# Bargraph.net
KiCad netlist of a schematic drawn in Altium Designer
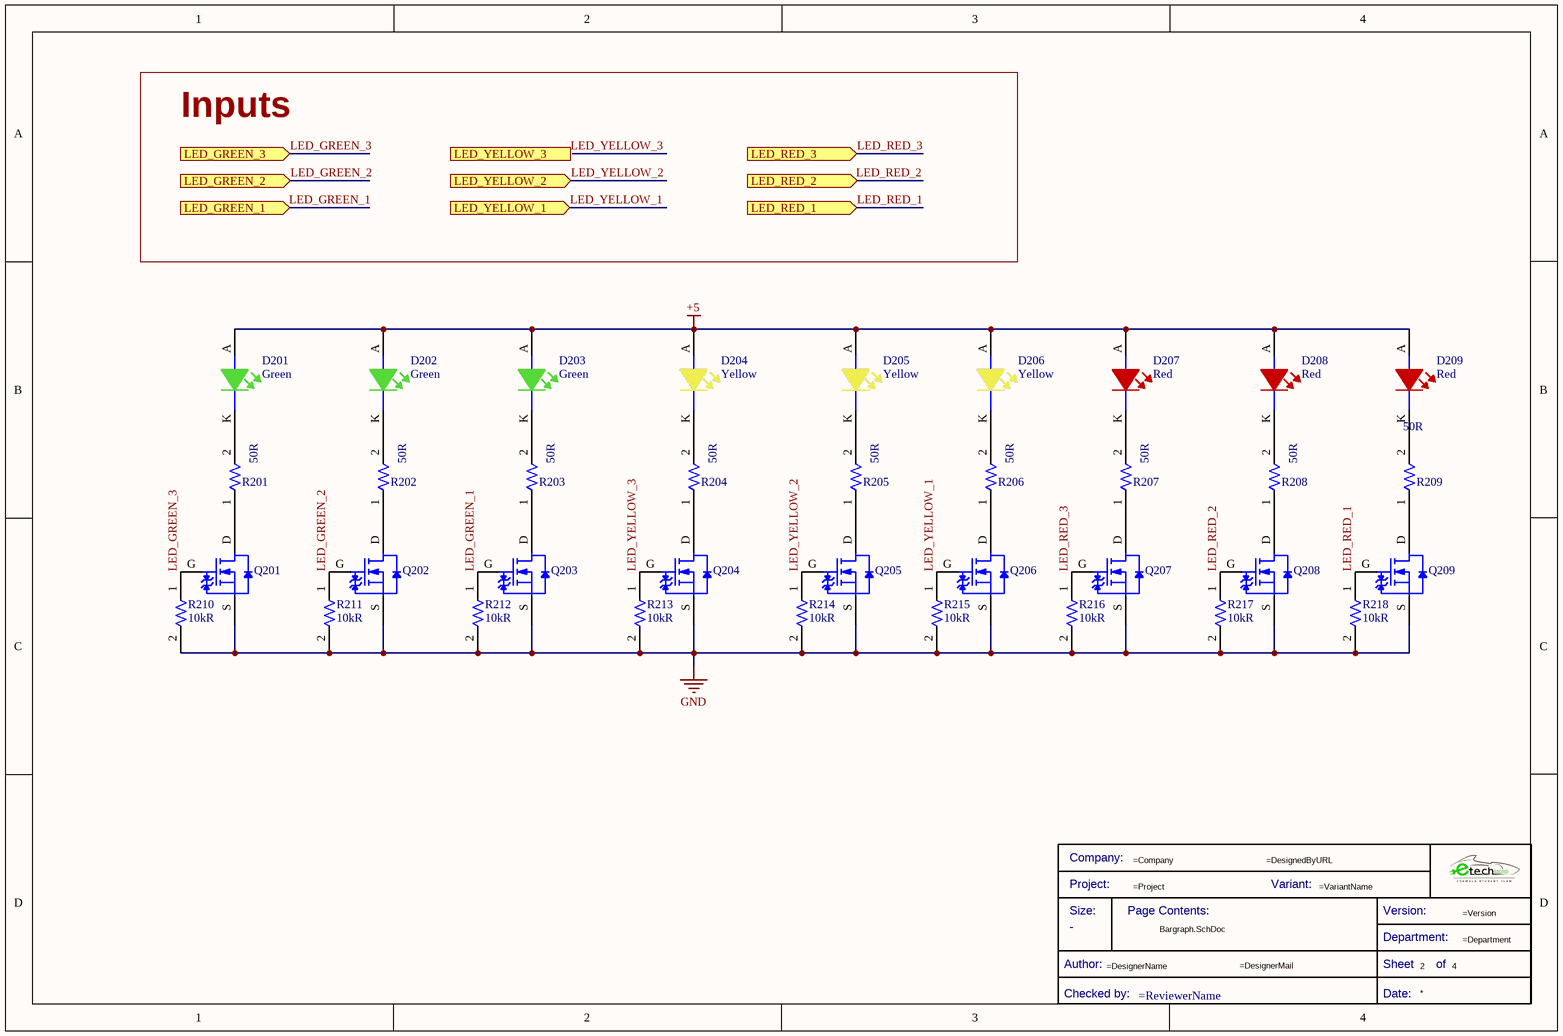
[diagram p0: Bargraph.SchDoc]

(export (version "E")
  (design (tool "Eeschema 10.0.6"))
  (components
    (comp (ref "D201")
      (value "150080GS75000")
      (footprint "LED-THT/WE/D3.9H10.5")
      (description "Led, Green, 520 Nm, 3.2 V, 30 Ma, 450 Mcd Rohs Compliant: Yes")
      (fields (field (name "COLOR") "Green") (field (name ".CREATOR") "GP"))
      (libsource (lib "Semiconductor") (part "LEDGS-THT"))
    )
    (comp (ref "D202")
      (value "150080GS75000")
      (footprint "LED-THT/WE/D3.9H10.5")
      (description "Led, Green, 520 Nm, 3.2 V, 30 Ma, 450 Mcd Rohs Compliant: Yes")
      (fields (field (name "COLOR") "Green") (field (name ".CREATOR") "GP"))
      (libsource (lib "Semiconductor") (part "LEDGS-THT"))
    )
    (comp (ref "D203")
      (value "150080GS75000")
      (footprint "LED-THT/WE/D3.9H10.5")
      (description "Led, Green, 520 Nm, 3.2 V, 30 Ma, 450 Mcd Rohs Compliant: Yes")
      (fields (field (name "COLOR") "Green") (field (name ".CREATOR") "GP"))
      (libsource (lib "Semiconductor") (part "LEDGS-THT"))
    )
    (comp (ref "D204")
      (value "150080YS75000")
      (footprint "LED-THT/WE/D3.9H10.5")
      (description "2 V Yellow LED 2012 (0805) SMD, Wurth Elektronik WL-SMCW 150080YS75000")
      (fields (field (name "COLOR") "Yellow") (field (name ".CREATOR") "DR"))
      (libsource (lib "Semiconductor") (part "LEDYS-THT"))
    )
    (comp (ref "D205")
      (value "150080YS75000")
      (footprint "LED-THT/WE/D3.9H10.5")
      (description "2 V Yellow LED 2012 (0805) SMD, Wurth Elektronik WL-SMCW 150080YS75000")
      (fields (field (name "COLOR") "Yellow") (field (name ".CREATOR") "DR"))
      (libsource (lib "Semiconductor") (part "LEDYS-THT"))
    )
    (comp (ref "D206")
      (value "150080YS75000")
      (footprint "LED-THT/WE/D3.9H10.5")
      (description "2 V Yellow LED 2012 (0805) SMD, Wurth Elektronik WL-SMCW 150080YS75000")
      (fields (field (name "COLOR") "Yellow") (field (name ".CREATOR") "DR"))
      (libsource (lib "Semiconductor") (part "LEDYS-THT"))
    )
    (comp (ref "D207")
      (value "150080RS75000")
      (footprint "LED-THT/WE/D3.9H10.5")
      (description "0805(H=0.8mm) 红色 高亮 λD=625nm VF=2V IF=30mA PD=72mW")
      (fields (field (name "COLOR") "Red") (field (name ".CREATOR") "DR"))
      (libsource (lib "Semiconductor") (part "LEDRS-THT"))
    )
    (comp (ref "D208")
      (value "150080RS75000")
      (footprint "LED-THT/WE/D3.9H10.5")
      (description "0805(H=0.8mm) 红色 高亮 λD=625nm VF=2V IF=30mA PD=72mW")
      (fields (field (name "COLOR") "Red") (field (name ".CREATOR") "DR"))
      (libsource (lib "Semiconductor") (part "LEDRS-THT"))
    )
    (comp (ref "D209")
      (value "150080RS75000")
      (footprint "LED-THT/WE/D3.9H10.5")
      (description "0805(H=0.8mm) 红色 高亮 λD=625nm VF=2V IF=30mA PD=72mW")
      (fields (field (name "COLOR") "Red") (field (name ".CREATOR") "DR"))
      (libsource (lib "Semiconductor") (part "LEDRS-THT"))
    )
    (comp (ref "Q201")
      (value "CPH3455-TL-H")
      (footprint "TRT-NCH-3/35-CPH")
      (description "CPH3455-TL-H N-channel MOSFET Transistor; 3 A; 35 V; 3-Pin CPH")
      (fields (field (name "MANUFACTURER") "ON Semiconductor") (field (name ".CREATOR") "GP"))
      (libsource (lib "Semiconductor") (part "TRT-NCH-3/35-CPH"))
    )
    (comp (ref "Q202")
      (value "CPH3455-TL-H")
      (footprint "TRT-NCH-3/35-CPH")
      (description "CPH3455-TL-H N-channel MOSFET Transistor; 3 A; 35 V; 3-Pin CPH")
      (fields (field (name "MANUFACTURER") "ON Semiconductor") (field (name ".CREATOR") "GP"))
      (libsource (lib "Semiconductor") (part "TRT-NCH-3/35-CPH"))
    )
    (comp (ref "Q203")
      (value "CPH3455-TL-H")
      (footprint "TRT-NCH-3/35-CPH")
      (description "CPH3455-TL-H N-channel MOSFET Transistor; 3 A; 35 V; 3-Pin CPH")
      (fields (field (name "MANUFACTURER") "ON Semiconductor") (field (name ".CREATOR") "GP"))
      (libsource (lib "Semiconductor") (part "TRT-NCH-3/35-CPH"))
    )
    (comp (ref "Q204")
      (value "CPH3455-TL-H")
      (footprint "TRT-NCH-3/35-CPH")
      (description "CPH3455-TL-H N-channel MOSFET Transistor; 3 A; 35 V; 3-Pin CPH")
      (fields (field (name "MANUFACTURER") "ON Semiconductor") (field (name ".CREATOR") "GP"))
      (libsource (lib "Semiconductor") (part "TRT-NCH-3/35-CPH"))
    )
    (comp (ref "Q205")
      (value "CPH3455-TL-H")
      (footprint "TRT-NCH-3/35-CPH")
      (description "CPH3455-TL-H N-channel MOSFET Transistor; 3 A; 35 V; 3-Pin CPH")
      (fields (field (name "MANUFACTURER") "ON Semiconductor") (field (name ".CREATOR") "GP"))
      (libsource (lib "Semiconductor") (part "TRT-NCH-3/35-CPH"))
    )
    (comp (ref "Q206")
      (value "CPH3455-TL-H")
      (footprint "TRT-NCH-3/35-CPH")
      (description "CPH3455-TL-H N-channel MOSFET Transistor; 3 A; 35 V; 3-Pin CPH")
      (fields (field (name "MANUFACTURER") "ON Semiconductor") (field (name ".CREATOR") "GP"))
      (libsource (lib "Semiconductor") (part "TRT-NCH-3/35-CPH"))
    )
    (comp (ref "Q207")
      (value "CPH3455-TL-H")
      (footprint "TRT-NCH-3/35-CPH")
      (description "CPH3455-TL-H N-channel MOSFET Transistor; 3 A; 35 V; 3-Pin CPH")
      (fields (field (name "MANUFACTURER") "ON Semiconductor") (field (name ".CREATOR") "GP"))
      (libsource (lib "Semiconductor") (part "TRT-NCH-3/35-CPH"))
    )
    (comp (ref "Q208")
      (value "CPH3455-TL-H")
      (footprint "TRT-NCH-3/35-CPH")
      (description "CPH3455-TL-H N-channel MOSFET Transistor; 3 A; 35 V; 3-Pin CPH")
      (fields (field (name "MANUFACTURER") "ON Semiconductor") (field (name ".CREATOR") "GP"))
      (libsource (lib "Semiconductor") (part "TRT-NCH-3/35-CPH"))
    )
    (comp (ref "Q209")
      (value "CPH3455-TL-H")
      (footprint "TRT-NCH-3/35-CPH")
      (description "CPH3455-TL-H N-channel MOSFET Transistor; 3 A; 35 V; 3-Pin CPH")
      (fields (field (name "MANUFACTURER") "ON Semiconductor") (field (name ".CREATOR") "GP"))
      (libsource (lib "Semiconductor") (part "TRT-NCH-3/35-CPH"))
    )
    (comp (ref "R201")
      (value "50R")
      (footprint "R0805FTK")
      (description "Res Thick Film 0805 50 Ohm 1% 0.125W(1/8W) ±100ppm/C Pad SMD Automotive T/R")
      (fields
        (field (name "MANUFACTURER") "Vishay Dale")
        (field (name "MANUFACTURER PART NUMBER") "CRCW080550R0FKTA")
      )
      (libsource (lib "Passives") (part "R50-0805FTK"))
    )
    (comp (ref "R202")
      (value "50R")
      (footprint "R0805FTK")
      (description "Res Thick Film 0805 50 Ohm 1% 0.125W(1/8W) ±100ppm/C Pad SMD Automotive T/R")
      (fields
        (field (name "MANUFACTURER") "Vishay Dale")
        (field (name "MANUFACTURER PART NUMBER") "CRCW080550R0FKTA")
      )
      (libsource (lib "Passives") (part "R50-0805FTK"))
    )
    (comp (ref "R203")
      (value "50R")
      (footprint "R0805FTK")
      (description "Res Thick Film 0805 50 Ohm 1% 0.125W(1/8W) ±100ppm/C Pad SMD Automotive T/R")
      (fields
        (field (name "MANUFACTURER") "Vishay Dale")
        (field (name "MANUFACTURER PART NUMBER") "CRCW080550R0FKTA")
      )
      (libsource (lib "Passives") (part "R50-0805FTK"))
    )
    (comp (ref "R204")
      (value "50R")
      (footprint "R0805FTK")
      (description "Res Thick Film 0805 50 Ohm 1% 0.125W(1/8W) ±100ppm/C Pad SMD Automotive T/R")
      (fields
        (field (name "MANUFACTURER") "Vishay Dale")
        (field (name "MANUFACTURER PART NUMBER") "CRCW080550R0FKTA")
      )
      (libsource (lib "Passives") (part "R50-0805FTK"))
    )
    (comp (ref "R205")
      (value "50R")
      (footprint "R0805FTK")
      (description "Res Thick Film 0805 50 Ohm 1% 0.125W(1/8W) ±100ppm/C Pad SMD Automotive T/R")
      (fields
        (field (name "MANUFACTURER") "Vishay Dale")
        (field (name "MANUFACTURER PART NUMBER") "CRCW080550R0FKTA")
      )
      (libsource (lib "Passives") (part "R50-0805FTK"))
    )
    (comp (ref "R206")
      (value "50R")
      (footprint "R0805FTK")
      (description "Res Thick Film 0805 50 Ohm 1% 0.125W(1/8W) ±100ppm/C Pad SMD Automotive T/R")
      (fields
        (field (name "MANUFACTURER") "Vishay Dale")
        (field (name "MANUFACTURER PART NUMBER") "CRCW080550R0FKTA")
      )
      (libsource (lib "Passives") (part "R50-0805FTK"))
    )
    (comp (ref "R207")
      (value "50R")
      (footprint "R0805FTK")
      (description "Res Thick Film 0805 50 Ohm 1% 0.125W(1/8W) ±100ppm/C Pad SMD Automotive T/R")
      (fields
        (field (name "MANUFACTURER") "Vishay Dale")
        (field (name "MANUFACTURER PART NUMBER") "CRCW080550R0FKTA")
      )
      (libsource (lib "Passives") (part "R50-0805FTK"))
    )
    (comp (ref "R208")
      (value "50R")
      (footprint "R0805FTK")
      (description "Res Thick Film 0805 50 Ohm 1% 0.125W(1/8W) ±100ppm/C Pad SMD Automotive T/R")
      (fields
        (field (name "MANUFACTURER") "Vishay Dale")
        (field (name "MANUFACTURER PART NUMBER") "CRCW080550R0FKTA")
      )
      (libsource (lib "Passives") (part "R50-0805FTK"))
    )
    (comp (ref "R209")
      (value "50R")
      (footprint "R0805FTK")
      (description "Res Thick Film 0805 50 Ohm 1% 0.125W(1/8W) ±100ppm/C Pad SMD Automotive T/R")
      (fields
        (field (name "MANUFACTURER") "Vishay Dale")
        (field (name "MANUFACTURER PART NUMBER") "CRCW080550R0FKTA")
      )
      (libsource (lib "Passives") (part "R50-0805FTK"))
    )
    (comp (ref "R210")
      (value "CR0805-JW-103ELF")
      (footprint "R0805FTK")
      (fields
        (field (name "TOLERANCE") "5%")
        (field (name "RESISTANCE") "10kR")
        (field (name ".CREATOR") "DR")
      )
      (libsource (lib "Passives") (part "R10k-0805FTK"))
    )
    (comp (ref "R211")
      (value "CR0805-JW-103ELF")
      (footprint "R0805FTK")
      (fields
        (field (name "TOLERANCE") "5%")
        (field (name "RESISTANCE") "10kR")
        (field (name ".CREATOR") "DR")
      )
      (libsource (lib "Passives") (part "R10k-0805FTK"))
    )
    (comp (ref "R212")
      (value "CR0805-JW-103ELF")
      (footprint "R0805FTK")
      (fields
        (field (name "TOLERANCE") "5%")
        (field (name "RESISTANCE") "10kR")
        (field (name ".CREATOR") "DR")
      )
      (libsource (lib "Passives") (part "R10k-0805FTK"))
    )
    (comp (ref "R213")
      (value "CR0805-JW-103ELF")
      (footprint "R0805FTK")
      (fields
        (field (name "TOLERANCE") "5%")
        (field (name "RESISTANCE") "10kR")
        (field (name ".CREATOR") "DR")
      )
      (libsource (lib "Passives") (part "R10k-0805FTK"))
    )
    (comp (ref "R214")
      (value "CR0805-JW-103ELF")
      (footprint "R0805FTK")
      (fields
        (field (name "TOLERANCE") "5%")
        (field (name "RESISTANCE") "10kR")
        (field (name ".CREATOR") "DR")
      )
      (libsource (lib "Passives") (part "R10k-0805FTK"))
    )
    (comp (ref "R215")
      (value "CR0805-JW-103ELF")
      (footprint "R0805FTK")
      (fields
        (field (name "TOLERANCE") "5%")
        (field (name "RESISTANCE") "10kR")
        (field (name ".CREATOR") "DR")
      )
      (libsource (lib "Passives") (part "R10k-0805FTK"))
    )
    (comp (ref "R216")
      (value "CR0805-JW-103ELF")
      (footprint "R0805FTK")
      (fields
        (field (name "TOLERANCE") "5%")
        (field (name "RESISTANCE") "10kR")
        (field (name ".CREATOR") "DR")
      )
      (libsource (lib "Passives") (part "R10k-0805FTK"))
    )
    (comp (ref "R217")
      (value "CR0805-JW-103ELF")
      (footprint "R0805FTK")
      (fields
        (field (name "TOLERANCE") "5%")
        (field (name "RESISTANCE") "10kR")
        (field (name ".CREATOR") "DR")
      )
      (libsource (lib "Passives") (part "R10k-0805FTK"))
    )
    (comp (ref "R218")
      (value "CR0805-JW-103ELF")
      (footprint "R0805FTK")
      (fields
        (field (name "TOLERANCE") "5%")
        (field (name "RESISTANCE") "10kR")
        (field (name ".CREATOR") "DR")
      )
      (libsource (lib "Passives") (part "R10k-0805FTK"))
    )
  )
  (nets
    (net (code "1") (name "+5") (class "Default")
      (node (ref "D201") (pin "A") (pinfunction "A_A") (pintype "passive"))
      (node (ref "D202") (pin "A") (pinfunction "A_A") (pintype "passive"))
      (node (ref "D203") (pin "A") (pinfunction "A_A") (pintype "passive"))
      (node (ref "D204") (pin "A") (pinfunction "A_A") (pintype "passive"))
      (node (ref "D205") (pin "A") (pinfunction "A_A") (pintype "passive"))
      (node (ref "D206") (pin "A") (pinfunction "A_A") (pintype "passive"))
      (node (ref "D207") (pin "A") (pinfunction "A_A") (pintype "passive"))
      (node (ref "D208") (pin "A") (pinfunction "A_A") (pintype "passive"))
      (node (ref "D209") (pin "A") (pinfunction "A_A") (pintype "passive"))
    )
    (net (code "2") (name "/LED_GREEN_1") (class "Default")
      (node (ref "Q203") (pin "G") (pinfunction "G_G") (pintype "passive"))
      (node (ref "R212") (pin "1") (pinfunction "1_1") (pintype "passive"))
    )
    (net (code "3") (name "/LED_GREEN_2") (class "Default")
      (node (ref "Q202") (pin "G") (pinfunction "G_G") (pintype "passive"))
      (node (ref "R211") (pin "1") (pinfunction "1_1") (pintype "passive"))
    )
    (net (code "4") (name "/LED_GREEN_3") (class "Default")
      (node (ref "Q201") (pin "G") (pinfunction "G_G") (pintype "passive"))
      (node (ref "R210") (pin "1") (pinfunction "1_1") (pintype "passive"))
    )
    (net (code "5") (name "/LED_RED_1") (class "Default")
      (node (ref "Q209") (pin "G") (pinfunction "G_G") (pintype "passive"))
      (node (ref "R218") (pin "1") (pinfunction "1_1") (pintype "passive"))
    )
    (net (code "6") (name "/LED_RED_2") (class "Default")
      (node (ref "Q208") (pin "G") (pinfunction "G_G") (pintype "passive"))
      (node (ref "R217") (pin "1") (pinfunction "1_1") (pintype "passive"))
    )
    (net (code "7") (name "/LED_RED_3") (class "Default")
      (node (ref "Q207") (pin "G") (pinfunction "G_G") (pintype "passive"))
      (node (ref "R216") (pin "1") (pinfunction "1_1") (pintype "passive"))
    )
    (net (code "8") (name "/LED_YELLOW_1") (class "Default")
      (node (ref "Q206") (pin "G") (pinfunction "G_G") (pintype "passive"))
      (node (ref "R215") (pin "1") (pinfunction "1_1") (pintype "passive"))
    )
    (net (code "9") (name "/LED_YELLOW_2") (class "Default")
      (node (ref "Q205") (pin "G") (pinfunction "G_G") (pintype "passive"))
      (node (ref "R214") (pin "1") (pinfunction "1_1") (pintype "passive"))
    )
    (net (code "10") (name "/LED_YELLOW_3") (class "Default")
      (node (ref "Q204") (pin "G") (pinfunction "G_G") (pintype "passive"))
      (node (ref "R213") (pin "1") (pinfunction "1_1") (pintype "passive"))
    )
    (net (code "11") (name "GND") (class "Default")
      (node (ref "Q201") (pin "S") (pinfunction "S_S") (pintype "passive"))
      (node (ref "Q202") (pin "S") (pinfunction "S_S") (pintype "passive"))
      (node (ref "Q203") (pin "S") (pinfunction "S_S") (pintype "passive"))
      (node (ref "Q204") (pin "S") (pinfunction "S_S") (pintype "passive"))
      (node (ref "Q205") (pin "S") (pinfunction "S_S") (pintype "passive"))
      (node (ref "Q206") (pin "S") (pinfunction "S_S") (pintype "passive"))
      (node (ref "Q207") (pin "S") (pinfunction "S_S") (pintype "passive"))
      (node (ref "Q208") (pin "S") (pinfunction "S_S") (pintype "passive"))
      (node (ref "Q209") (pin "S") (pinfunction "S_S") (pintype "passive"))
      (node (ref "R210") (pin "2") (pinfunction "2_2") (pintype "passive"))
      (node (ref "R211") (pin "2") (pinfunction "2_2") (pintype "passive"))
      (node (ref "R212") (pin "2") (pinfunction "2_2") (pintype "passive"))
      (node (ref "R213") (pin "2") (pinfunction "2_2") (pintype "passive"))
      (node (ref "R214") (pin "2") (pinfunction "2_2") (pintype "passive"))
      (node (ref "R215") (pin "2") (pinfunction "2_2") (pintype "passive"))
      (node (ref "R216") (pin "2") (pinfunction "2_2") (pintype "passive"))
      (node (ref "R217") (pin "2") (pinfunction "2_2") (pintype "passive"))
      (node (ref "R218") (pin "2") (pinfunction "2_2") (pintype "passive"))
    )
    (net (code "12") (name "Net-(D201-PadK)") (class "Default")
      (node (ref "D201") (pin "K") (pinfunction "K_K") (pintype "passive"))
      (node (ref "R201") (pin "2") (pinfunction "2_2") (pintype "passive"))
    )
    (net (code "13") (name "Net-(D202-PadK)") (class "Default")
      (node (ref "D202") (pin "K") (pinfunction "K_K") (pintype "passive"))
      (node (ref "R202") (pin "2") (pinfunction "2_2") (pintype "passive"))
    )
    (net (code "14") (name "Net-(D203-PadK)") (class "Default")
      (node (ref "D203") (pin "K") (pinfunction "K_K") (pintype "passive"))
      (node (ref "R203") (pin "2") (pinfunction "2_2") (pintype "passive"))
    )
    (net (code "15") (name "Net-(D204-PadK)") (class "Default")
      (node (ref "D204") (pin "K") (pinfunction "K_K") (pintype "passive"))
      (node (ref "R204") (pin "2") (pinfunction "2_2") (pintype "passive"))
    )
    (net (code "16") (name "Net-(D205-PadK)") (class "Default")
      (node (ref "D205") (pin "K") (pinfunction "K_K") (pintype "passive"))
      (node (ref "R205") (pin "2") (pinfunction "2_2") (pintype "passive"))
    )
    (net (code "17") (name "Net-(D206-PadK)") (class "Default")
      (node (ref "D206") (pin "K") (pinfunction "K_K") (pintype "passive"))
      (node (ref "R206") (pin "2") (pinfunction "2_2") (pintype "passive"))
    )
    (net (code "18") (name "Net-(D207-PadK)") (class "Default")
      (node (ref "D207") (pin "K") (pinfunction "K_K") (pintype "passive"))
      (node (ref "R207") (pin "2") (pinfunction "2_2") (pintype "passive"))
    )
    (net (code "19") (name "Net-(D208-PadK)") (class "Default")
      (node (ref "D208") (pin "K") (pinfunction "K_K") (pintype "passive"))
      (node (ref "R208") (pin "2") (pinfunction "2_2") (pintype "passive"))
    )
    (net (code "20") (name "Net-(D209-PadK)") (class "Default")
      (node (ref "D209") (pin "K") (pinfunction "K_K") (pintype "passive"))
      (node (ref "R209") (pin "2") (pinfunction "2_2") (pintype "passive"))
    )
    (net (code "21") (name "Net-(Q201-PadD)") (class "Default")
      (node (ref "Q201") (pin "D") (pinfunction "D_D") (pintype "passive"))
      (node (ref "R201") (pin "1") (pinfunction "1_1") (pintype "passive"))
    )
    (net (code "22") (name "Net-(Q202-PadD)") (class "Default")
      (node (ref "Q202") (pin "D") (pinfunction "D_D") (pintype "passive"))
      (node (ref "R202") (pin "1") (pinfunction "1_1") (pintype "passive"))
    )
    (net (code "23") (name "Net-(Q203-PadD)") (class "Default")
      (node (ref "Q203") (pin "D") (pinfunction "D_D") (pintype "passive"))
      (node (ref "R203") (pin "1") (pinfunction "1_1") (pintype "passive"))
    )
    (net (code "24") (name "Net-(Q204-PadD)") (class "Default")
      (node (ref "Q204") (pin "D") (pinfunction "D_D") (pintype "passive"))
      (node (ref "R204") (pin "1") (pinfunction "1_1") (pintype "passive"))
    )
    (net (code "25") (name "Net-(Q205-PadD)") (class "Default")
      (node (ref "Q205") (pin "D") (pinfunction "D_D") (pintype "passive"))
      (node (ref "R205") (pin "1") (pinfunction "1_1") (pintype "passive"))
    )
    (net (code "26") (name "Net-(Q206-PadD)") (class "Default")
      (node (ref "Q206") (pin "D") (pinfunction "D_D") (pintype "passive"))
      (node (ref "R206") (pin "1") (pinfunction "1_1") (pintype "passive"))
    )
    (net (code "27") (name "Net-(Q207-PadD)") (class "Default")
      (node (ref "Q207") (pin "D") (pinfunction "D_D") (pintype "passive"))
      (node (ref "R207") (pin "1") (pinfunction "1_1") (pintype "passive"))
    )
    (net (code "28") (name "Net-(Q208-PadD)") (class "Default")
      (node (ref "Q208") (pin "D") (pinfunction "D_D") (pintype "passive"))
      (node (ref "R208") (pin "1") (pinfunction "1_1") (pintype "passive"))
    )
    (net (code "29") (name "Net-(Q209-PadD)") (class "Default")
      (node (ref "Q209") (pin "D") (pinfunction "D_D") (pintype "passive"))
      (node (ref "R209") (pin "1") (pinfunction "1_1") (pintype "passive"))
    )
  )
)
